# 5_Relays_Shutdown.net
KiCad netlist of a schematic drawn in Altium Designer
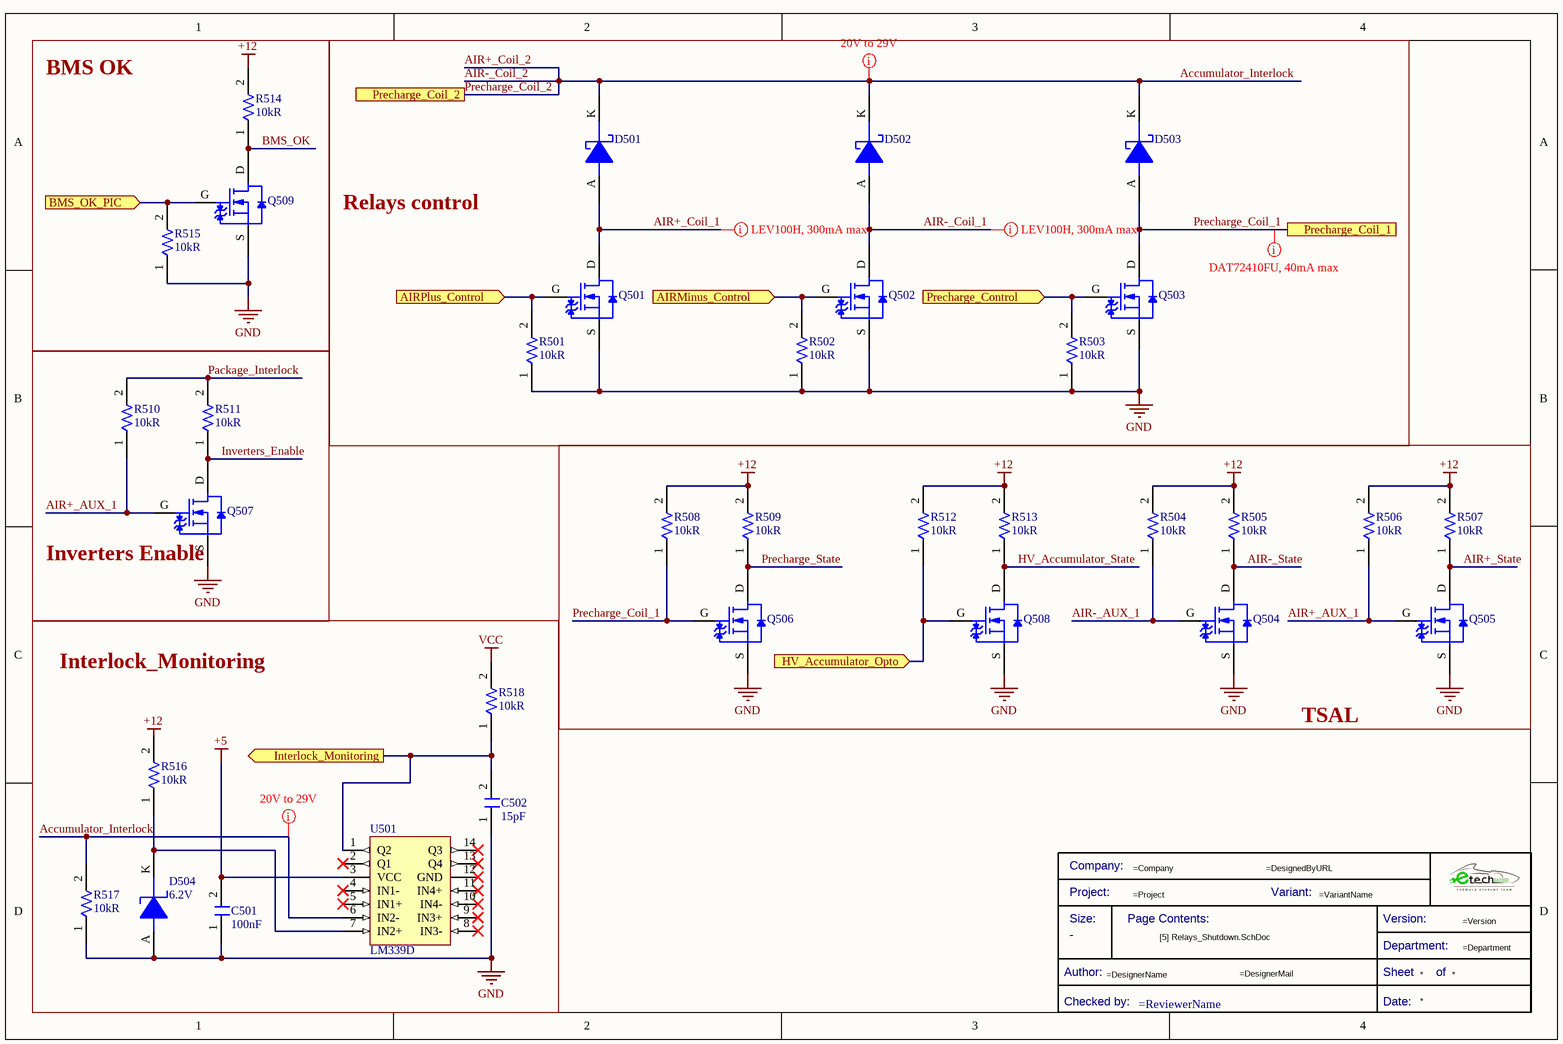
[diagram p0: [5] Relays_Shutdown.SchDoc]

(export (version "E")
  (design (tool "Eeschema 10.0.6"))
  (components
    (comp (ref "*")
      (value "Title Block_template")
      (description "Standard Title Block")
      (fields (field (name "SIZE") "-"))
      (libsource (lib "e-Tech_Racing") (part "Title Block_template"))
    )
    (comp (ref "C501")
      (value "885012207098")
      (footprint "C0805FNPC-R")
      (description "Cap, 0.1ΜF, 50V, 10%, X7R, 0805")
      (fields
        (field (name "TOLERANCE") "10%")
        (field (name "CAPACITANCE") "100nF")
        (field (name ".CREATOR") "DR")
      )
      (libsource (lib "Passives") (part "C100n-50V-0805FNPC-X7R"))
    )
    (comp (ref "C502")
      (value "885012007052")
      (footprint "C0805FNPC-R")
      (description "Cap, 15PF, 50V, 5%, C0G/NP0, 0805")
      (fields
        (field (name "TOLERANCE") "5%")
        (field (name "CAPACITANCE") "15pF")
        (field (name ".CREATOR") "DR")
      )
      (libsource (lib "Passives") (part "C15p-50V-0805FNPC-NP0"))
    )
    (comp (ref "D501")
      (value "CMDSH05-4 TR PBFREE")
      (footprint "DSC-0.5/40-SOD_323")
      (description "CMDSH Series 40 V 500 mA Surface Mount Schottky Diode - SOD-323")
      (fields
        (field (name "MANUFACTURER") "Central Semiconductor")
        (field (name "MANUFACTURER PART NUMBER") "CMDSH05-4TR")
        (field (name ".CREATOR") "GP")
      )
      (libsource (lib "Semiconductor") (part "DSC-0.5/40-SOD_323"))
    )
    (comp (ref "D502")
      (value "CMDSH05-4 TR PBFREE")
      (footprint "DSC-0.5/40-SOD_323")
      (description "CMDSH Series 40 V 500 mA Surface Mount Schottky Diode - SOD-323")
      (fields
        (field (name "MANUFACTURER") "Central Semiconductor")
        (field (name "MANUFACTURER PART NUMBER") "CMDSH05-4TR")
        (field (name ".CREATOR") "GP")
      )
      (libsource (lib "Semiconductor") (part "DSC-0.5/40-SOD_323"))
    )
    (comp (ref "D503")
      (value "CMDSH05-4 TR PBFREE")
      (footprint "DSC-0.5/40-SOD_323")
      (description "CMDSH Series 40 V 500 mA Surface Mount Schottky Diode - SOD-323")
      (fields
        (field (name "MANUFACTURER") "Central Semiconductor")
        (field (name "MANUFACTURER PART NUMBER") "CMDSH05-4TR")
        (field (name ".CREATOR") "GP")
      )
      (libsource (lib "Semiconductor") (part "DSC-0.5/40-SOD_323"))
    )
    (comp (ref "D504")
      (value "BZG05C6V2-E3-TR")
      (description "BZG05C Series 6.2 V 200 mA Surface Mount Zener Diode - DO-214AC")
      (fields
        (field (name "TOLERANCE") "5%")
        (field (name "ZENER VOLTAGE") "6.2V")
        (field (name ".CREATOR") "DO")
      )
      (libsource (lib "Semiconductor") (part "DZ-6.2V-DO-214AC"))
    )
    (comp (ref "Q501")
      (value "CPH3455-TL-H")
      (footprint "TRT-NCH-3/35-CPH")
      (description "CPH3455-TL-H N-channel MOSFET Transistor; 3 A; 35 V; 3-Pin CPH")
      (fields (field (name "MANUFACTURER") "ON Semiconductor") (field (name ".CREATOR") "GP"))
      (libsource (lib "Semiconductor") (part "TRT-NCH-3/35-CPH"))
    )
    (comp (ref "Q502")
      (value "CPH3455-TL-H")
      (footprint "TRT-NCH-3/35-CPH")
      (description "CPH3455-TL-H N-channel MOSFET Transistor; 3 A; 35 V; 3-Pin CPH")
      (fields (field (name "MANUFACTURER") "ON Semiconductor") (field (name ".CREATOR") "GP"))
      (libsource (lib "Semiconductor") (part "TRT-NCH-3/35-CPH"))
    )
    (comp (ref "Q503")
      (value "CPH3455-TL-H")
      (footprint "TRT-NCH-3/35-CPH")
      (description "CPH3455-TL-H N-channel MOSFET Transistor; 3 A; 35 V; 3-Pin CPH")
      (fields (field (name "MANUFACTURER") "ON Semiconductor") (field (name ".CREATOR") "GP"))
      (libsource (lib "Semiconductor") (part "TRT-NCH-3/35-CPH"))
    )
    (comp (ref "Q504")
      (value "CPH3455-TL-H")
      (footprint "TRT-NCH-3/35-CPH")
      (description "CPH3455-TL-H N-channel MOSFET Transistor; 3 A; 35 V; 3-Pin CPH")
      (fields (field (name "MANUFACTURER") "ON Semiconductor") (field (name ".CREATOR") "GP"))
      (libsource (lib "Semiconductor") (part "TRT-NCH-3/35-CPH"))
    )
    (comp (ref "Q505")
      (value "CPH3455-TL-H")
      (footprint "TRT-NCH-3/35-CPH")
      (description "CPH3455-TL-H N-channel MOSFET Transistor; 3 A; 35 V; 3-Pin CPH")
      (fields (field (name "MANUFACTURER") "ON Semiconductor") (field (name ".CREATOR") "GP"))
      (libsource (lib "Semiconductor") (part "TRT-NCH-3/35-CPH"))
    )
    (comp (ref "Q506")
      (value "CPH3455-TL-H")
      (footprint "TRT-NCH-3/35-CPH")
      (description "CPH3455-TL-H N-channel MOSFET Transistor; 3 A; 35 V; 3-Pin CPH")
      (fields (field (name "MANUFACTURER") "ON Semiconductor") (field (name ".CREATOR") "GP"))
      (libsource (lib "Semiconductor") (part "TRT-NCH-3/35-CPH"))
    )
    (comp (ref "Q507")
      (value "CPH3455-TL-H")
      (footprint "TRT-NCH-3/35-CPH")
      (description "CPH3455-TL-H N-channel MOSFET Transistor; 3 A; 35 V; 3-Pin CPH")
      (fields (field (name "MANUFACTURER") "ON Semiconductor") (field (name ".CREATOR") "GP"))
      (libsource (lib "Semiconductor") (part "TRT-NCH-3/35-CPH"))
    )
    (comp (ref "Q508")
      (value "CPH3455-TL-H")
      (footprint "TRT-NCH-3/35-CPH")
      (description "CPH3455-TL-H N-channel MOSFET Transistor; 3 A; 35 V; 3-Pin CPH")
      (fields (field (name "MANUFACTURER") "ON Semiconductor") (field (name ".CREATOR") "GP"))
      (libsource (lib "Semiconductor") (part "TRT-NCH-3/35-CPH"))
    )
    (comp (ref "Q509")
      (value "CPH3455-TL-H")
      (footprint "TRT-NCH-3/35-CPH")
      (description "CPH3455-TL-H N-channel MOSFET Transistor; 3 A; 35 V; 3-Pin CPH")
      (fields (field (name "MANUFACTURER") "ON Semiconductor") (field (name ".CREATOR") "GP"))
      (libsource (lib "Semiconductor") (part "TRT-NCH-3/35-CPH"))
    )
    (comp (ref "R501")
      (value "CR0805-JW-103ELF")
      (footprint "R0805FTK")
      (fields
        (field (name "TOLERANCE") "5%")
        (field (name "RESISTANCE") "10kR")
        (field (name ".CREATOR") "DR")
      )
      (libsource (lib "Passives") (part "R10k-0805FTK"))
    )
    (comp (ref "R502")
      (value "CR0805-JW-103ELF")
      (footprint "R0805FTK")
      (fields
        (field (name "TOLERANCE") "5%")
        (field (name "RESISTANCE") "10kR")
        (field (name ".CREATOR") "DR")
      )
      (libsource (lib "Passives") (part "R10k-0805FTK"))
    )
    (comp (ref "R503")
      (value "CR0805-JW-103ELF")
      (footprint "R0805FTK")
      (fields
        (field (name "TOLERANCE") "5%")
        (field (name "RESISTANCE") "10kR")
        (field (name ".CREATOR") "DR")
      )
      (libsource (lib "Passives") (part "R10k-0805FTK"))
    )
    (comp (ref "R504")
      (value "CR0805-JW-103ELF")
      (footprint "R0805FTK")
      (fields
        (field (name "TOLERANCE") "5%")
        (field (name "RESISTANCE") "10kR")
        (field (name ".CREATOR") "DR")
      )
      (libsource (lib "Passives") (part "R10k-0805FTK"))
    )
    (comp (ref "R505")
      (value "CR0805-JW-103ELF")
      (footprint "R0805FTK")
      (fields
        (field (name "TOLERANCE") "5%")
        (field (name "RESISTANCE") "10kR")
        (field (name ".CREATOR") "DR")
      )
      (libsource (lib "Passives") (part "R10k-0805FTK"))
    )
    (comp (ref "R506")
      (value "CR0805-JW-103ELF")
      (footprint "R0805FTK")
      (fields
        (field (name "TOLERANCE") "5%")
        (field (name "RESISTANCE") "10kR")
        (field (name ".CREATOR") "DR")
      )
      (libsource (lib "Passives") (part "R10k-0805FTK"))
    )
    (comp (ref "R507")
      (value "CR0805-JW-103ELF")
      (footprint "R0805FTK")
      (fields
        (field (name "TOLERANCE") "5%")
        (field (name "RESISTANCE") "10kR")
        (field (name ".CREATOR") "DR")
      )
      (libsource (lib "Passives") (part "R10k-0805FTK"))
    )
    (comp (ref "R508")
      (value "CR0805-JW-103ELF")
      (footprint "R0805FTK")
      (fields
        (field (name "TOLERANCE") "5%")
        (field (name "RESISTANCE") "10kR")
        (field (name ".CREATOR") "DR")
      )
      (libsource (lib "Passives") (part "R10k-0805FTK"))
    )
    (comp (ref "R509")
      (value "CR0805-JW-103ELF")
      (footprint "R0805FTK")
      (fields
        (field (name "TOLERANCE") "5%")
        (field (name "RESISTANCE") "10kR")
        (field (name ".CREATOR") "DR")
      )
      (libsource (lib "Passives") (part "R10k-0805FTK"))
    )
    (comp (ref "R510")
      (value "CR0805-JW-103ELF")
      (footprint "R0805FTK")
      (fields
        (field (name "TOLERANCE") "5%")
        (field (name "RESISTANCE") "10kR")
        (field (name ".CREATOR") "DR")
      )
      (libsource (lib "Passives") (part "R10k-0805FTK"))
    )
    (comp (ref "R511")
      (value "CR0805-JW-103ELF")
      (footprint "R0805FTK")
      (fields
        (field (name "TOLERANCE") "5%")
        (field (name "RESISTANCE") "10kR")
        (field (name ".CREATOR") "DR")
      )
      (libsource (lib "Passives") (part "R10k-0805FTK"))
    )
    (comp (ref "R512")
      (value "CR0805-JW-103ELF")
      (footprint "R0805FTK")
      (fields
        (field (name "TOLERANCE") "5%")
        (field (name "RESISTANCE") "10kR")
        (field (name ".CREATOR") "DR")
      )
      (libsource (lib "Passives") (part "R10k-0805FTK"))
    )
    (comp (ref "R513")
      (value "CR0805-JW-103ELF")
      (footprint "R0805FTK")
      (fields
        (field (name "TOLERANCE") "5%")
        (field (name "RESISTANCE") "10kR")
        (field (name ".CREATOR") "DR")
      )
      (libsource (lib "Passives") (part "R10k-0805FTK"))
    )
    (comp (ref "R514")
      (value "CR0805-JW-103ELF")
      (footprint "R0805FTK")
      (fields
        (field (name "TOLERANCE") "5%")
        (field (name "RESISTANCE") "10kR")
        (field (name ".CREATOR") "DR")
      )
      (libsource (lib "Passives") (part "R10k-0805FTK"))
    )
    (comp (ref "R515")
      (value "CR0805-JW-103ELF")
      (footprint "R0805FTK")
      (fields
        (field (name "TOLERANCE") "5%")
        (field (name "RESISTANCE") "10kR")
        (field (name ".CREATOR") "DR")
      )
      (libsource (lib "Passives") (part "R10k-0805FTK"))
    )
    (comp (ref "R516")
      (value "CR0805-JW-103ELF")
      (footprint "R0805FTK")
      (fields
        (field (name "TOLERANCE") "5%")
        (field (name "RESISTANCE") "10kR")
        (field (name ".CREATOR") "DR")
      )
      (libsource (lib "Passives") (part "R10k-0805FTK"))
    )
    (comp (ref "R517")
      (value "CR0805-JW-103ELF")
      (footprint "R0805FTK")
      (fields
        (field (name "TOLERANCE") "5%")
        (field (name "RESISTANCE") "10kR")
        (field (name ".CREATOR") "DR")
      )
      (libsource (lib "Passives") (part "R10k-0805FTK"))
    )
    (comp (ref "R518")
      (value "CR0805-JW-103ELF")
      (footprint "R0805FTK")
      (fields
        (field (name "TOLERANCE") "5%")
        (field (name "RESISTANCE") "10kR")
        (field (name ".CREATOR") "DR")
      )
      (libsource (lib "Passives") (part "R10k-0805FTK"))
    )
    (comp (ref "U501")
      (value "LM339D")
      (footprint "Array_4_Amp_LM339D")
      (description "Comparator Quad ±18V/36V 14-Pin SOIC Tube")
      (fields
        (field (name "MANUFACTURER") "Texas Instruments")
        (field (name "MANUFACTURER PART NUMBER") "LM339D")
        (field (name ".CREATOR") "DO")
      )
      (libsource (lib "Integrated circuits") (part "Array_4_Amp_LM339D"))
    )
  )
  (nets
    (net (code "1") (name "+5") (class "Default")
      (node (ref "C501") (pin "2") (pinfunction "2_2") (pintype "passive"))
      (node (ref "U501") (pin "3") (pinfunction "VCC_3") (pintype "power_in"))
    )
    (net (code "2") (name "+12") (class "Default")
      (node (ref "R504") (pin "2") (pinfunction "2_2") (pintype "passive"))
      (node (ref "R505") (pin "2") (pinfunction "2_2") (pintype "passive"))
      (node (ref "R506") (pin "2") (pinfunction "2_2") (pintype "passive"))
      (node (ref "R507") (pin "2") (pinfunction "2_2") (pintype "passive"))
      (node (ref "R508") (pin "2") (pinfunction "2_2") (pintype "passive"))
      (node (ref "R509") (pin "2") (pinfunction "2_2") (pintype "passive"))
      (node (ref "R512") (pin "2") (pinfunction "2_2") (pintype "passive"))
      (node (ref "R513") (pin "2") (pinfunction "2_2") (pintype "passive"))
      (node (ref "R514") (pin "2") (pinfunction "2_2") (pintype "passive"))
    )
    (net (code "3") (name "/AIR+_AUX_1") (class "Default")
      (node (ref "Q505") (pin "G") (pinfunction "G_G") (pintype "passive"))
      (node (ref "Q507") (pin "G") (pinfunction "G_G") (pintype "passive"))
      (node (ref "R506") (pin "1") (pinfunction "1_1") (pintype "passive"))
      (node (ref "R510") (pin "1") (pinfunction "1_1") (pintype "passive"))
    )
    (net (code "4") (name "/AIR+_Coil_1") (class "Default")
      (node (ref "D501") (pin "A") (pinfunction "A_A") (pintype "passive"))
      (node (ref "Q501") (pin "D") (pinfunction "D_D") (pintype "passive"))
    )
    (net (code "5") (name "/AIR+_Coil_2") (class "Default")
      (node (ref "D501") (pin "K") (pinfunction "K_K") (pintype "passive"))
      (node (ref "D502") (pin "K") (pinfunction "K_K") (pintype "passive"))
      (node (ref "D503") (pin "K") (pinfunction "K_K") (pintype "passive"))
      (node (ref "R517") (pin "2") (pinfunction "2_2") (pintype "passive"))
      (node (ref "U501") (pin "6") (pinfunction "IN2-_6") (pintype "input"))
    )
    (net (code "6") (name "/AIR+_State") (class "Default")
      (node (ref "Q505") (pin "D") (pinfunction "D_D") (pintype "passive"))
      (node (ref "R507") (pin "1") (pinfunction "1_1") (pintype "passive"))
    )
    (net (code "7") (name "/AIR-_AUX_1") (class "Default")
      (node (ref "Q504") (pin "G") (pinfunction "G_G") (pintype "passive"))
      (node (ref "R504") (pin "1") (pinfunction "1_1") (pintype "passive"))
    )
    (net (code "8") (name "/AIR-_Coil_1") (class "Default")
      (node (ref "D502") (pin "A") (pinfunction "A_A") (pintype "passive"))
      (node (ref "Q502") (pin "D") (pinfunction "D_D") (pintype "passive"))
    )
    (net (code "9") (name "/AIR-_State") (class "Default")
      (node (ref "Q504") (pin "D") (pinfunction "D_D") (pintype "passive"))
      (node (ref "R505") (pin "1") (pinfunction "1_1") (pintype "passive"))
    )
    (net (code "10") (name "/AIRMinus_Control") (class "Default")
      (node (ref "Q502") (pin "G") (pinfunction "G_G") (pintype "passive"))
      (node (ref "R502") (pin "2") (pinfunction "2_2") (pintype "passive"))
    )
    (net (code "11") (name "/AIRPlus_Control") (class "Default")
      (node (ref "Q501") (pin "G") (pinfunction "G_G") (pintype "passive"))
      (node (ref "R501") (pin "2") (pinfunction "2_2") (pintype "passive"))
    )
    (net (code "12") (name "/BMS_OK") (class "Default")
      (node (ref "Q509") (pin "D") (pinfunction "D_D") (pintype "passive"))
      (node (ref "R514") (pin "1") (pinfunction "1_1") (pintype "passive"))
    )
    (net (code "13") (name "/BMS_OK_PIC") (class "Default")
      (node (ref "Q509") (pin "G") (pinfunction "G_G") (pintype "passive"))
      (node (ref "R515") (pin "2") (pinfunction "2_2") (pintype "passive"))
    )
    (net (code "14") (name "/HV_Accumulator_Opto") (class "Default")
      (node (ref "Q508") (pin "G") (pinfunction "G_G") (pintype "passive"))
      (node (ref "R512") (pin "1") (pinfunction "1_1") (pintype "passive"))
    )
    (net (code "15") (name "/HV_Accumulator_State") (class "Default")
      (node (ref "Q508") (pin "D") (pinfunction "D_D") (pintype "passive"))
      (node (ref "R513") (pin "1") (pinfunction "1_1") (pintype "passive"))
    )
    (net (code "16") (name "/Interlock_Monitoring") (class "Default")
      (node (ref "C502") (pin "2") (pinfunction "2_2") (pintype "passive"))
      (node (ref "R518") (pin "1") (pinfunction "1_1") (pintype "passive"))
      (node (ref "U501") (pin "1") (pinfunction "Q2_1") (pintype "output"))
    )
    (net (code "17") (name "/Inverters_Enable") (class "Default")
      (node (ref "Q507") (pin "D") (pinfunction "D_D") (pintype "passive"))
      (node (ref "R511") (pin "1") (pinfunction "1_1") (pintype "passive"))
    )
    (net (code "18") (name "/Package_Interlock") (class "Default")
      (node (ref "R510") (pin "2") (pinfunction "2_2") (pintype "passive"))
      (node (ref "R511") (pin "2") (pinfunction "2_2") (pintype "passive"))
    )
    (net (code "19") (name "/Precharge_Coil_1") (class "Default")
      (node (ref "D503") (pin "A") (pinfunction "A_A") (pintype "passive"))
      (node (ref "Q503") (pin "D") (pinfunction "D_D") (pintype "passive"))
      (node (ref "Q506") (pin "G") (pinfunction "G_G") (pintype "passive"))
      (node (ref "R508") (pin "1") (pinfunction "1_1") (pintype "passive"))
    )
    (net (code "20") (name "/Precharge_Control") (class "Default")
      (node (ref "Q503") (pin "G") (pinfunction "G_G") (pintype "passive"))
      (node (ref "R503") (pin "2") (pinfunction "2_2") (pintype "passive"))
    )
    (net (code "21") (name "/Precharge_State") (class "Default")
      (node (ref "Q506") (pin "D") (pinfunction "D_D") (pintype "passive"))
      (node (ref "R509") (pin "1") (pinfunction "1_1") (pintype "passive"))
    )
    (net (code "22") (name "GND") (class "Default")
      (node (ref "C501") (pin "1") (pinfunction "1_1") (pintype "passive"))
      (node (ref "C502") (pin "1") (pinfunction "1_1") (pintype "passive"))
      (node (ref "D504") (pin "A") (pinfunction "A_A") (pintype "passive"))
      (node (ref "Q501") (pin "S") (pinfunction "S_S") (pintype "passive"))
      (node (ref "Q502") (pin "S") (pinfunction "S_S") (pintype "passive"))
      (node (ref "Q503") (pin "S") (pinfunction "S_S") (pintype "passive"))
      (node (ref "Q504") (pin "S") (pinfunction "S_S") (pintype "passive"))
      (node (ref "Q505") (pin "S") (pinfunction "S_S") (pintype "passive"))
      (node (ref "Q506") (pin "S") (pinfunction "S_S") (pintype "passive"))
      (node (ref "Q507") (pin "S") (pinfunction "S_S") (pintype "passive"))
      (node (ref "Q508") (pin "S") (pinfunction "S_S") (pintype "passive"))
      (node (ref "Q509") (pin "S") (pinfunction "S_S") (pintype "passive"))
      (node (ref "R501") (pin "1") (pinfunction "1_1") (pintype "passive"))
      (node (ref "R502") (pin "1") (pinfunction "1_1") (pintype "passive"))
      (node (ref "R503") (pin "1") (pinfunction "1_1") (pintype "passive"))
      (node (ref "R515") (pin "1") (pinfunction "1_1") (pintype "passive"))
      (node (ref "R517") (pin "1") (pinfunction "1_1") (pintype "passive"))
    )
    (net (code "23") (name "Net-(U501-IN2+)") (class "Default")
      (node (ref "D504") (pin "K") (pinfunction "K_K") (pintype "passive"))
      (node (ref "R516") (pin "1") (pinfunction "1_1") (pintype "passive"))
      (node (ref "U501") (pin "7") (pinfunction "IN2+_7") (pintype "input"))
    )
    (net (code "24") (name "VCC") (class "Default")
      (node (ref "R518") (pin "2") (pinfunction "2_2") (pintype "passive"))
    )
    (net (code "25") (name "unconnected-(R516-Pad2)") (class "Default")
      (node (ref "R516") (pin "2") (pinfunction "2_2") (pintype "passive"))
    )
    (net (code "26") (name "unconnected-(U501-GND-Pad12)") (class "Default")
      (node (ref "U501") (pin "12") (pinfunction "GND_12") (pintype "power_in+no_connect"))
    )
    (net (code "27") (name "unconnected-(U501-IN1+-Pad5)") (class "Default")
      (node (ref "U501") (pin "5") (pinfunction "IN1+_5") (pintype "input+no_connect"))
    )
    (net (code "28") (name "unconnected-(U501-IN1--Pad4)") (class "Default")
      (node (ref "U501") (pin "4") (pinfunction "IN1-_4") (pintype "input+no_connect"))
    )
    (net (code "29") (name "unconnected-(U501-IN3+-Pad9)") (class "Default")
      (node (ref "U501") (pin "9") (pinfunction "IN3+_9") (pintype "input+no_connect"))
    )
    (net (code "30") (name "unconnected-(U501-IN3--Pad8)") (class "Default")
      (node (ref "U501") (pin "8") (pinfunction "IN3-_8") (pintype "input+no_connect"))
    )
    (net (code "31") (name "unconnected-(U501-IN4+-Pad11)") (class "Default")
      (node (ref "U501") (pin "11") (pinfunction "IN4+_11") (pintype "input+no_connect"))
    )
    (net (code "32") (name "unconnected-(U501-IN4--Pad10)") (class "Default")
      (node (ref "U501") (pin "10") (pinfunction "IN4-_10") (pintype "input+no_connect"))
    )
    (net (code "33") (name "unconnected-(U501-Q1-Pad2)") (class "Default")
      (node (ref "U501") (pin "2") (pinfunction "Q1_2") (pintype "output+no_connect"))
    )
    (net (code "34") (name "unconnected-(U501-Q3-Pad14)") (class "Default")
      (node (ref "U501") (pin "14") (pinfunction "Q3_14") (pintype "output+no_connect"))
    )
    (net (code "35") (name "unconnected-(U501-Q4-Pad13)") (class "Default")
      (node (ref "U501") (pin "13") (pinfunction "Q4_13") (pintype "output+no_connect"))
    )
  )
)
